# 05_POWER_2.net
KiCad netlist of a schematic drawn in Altium Designer
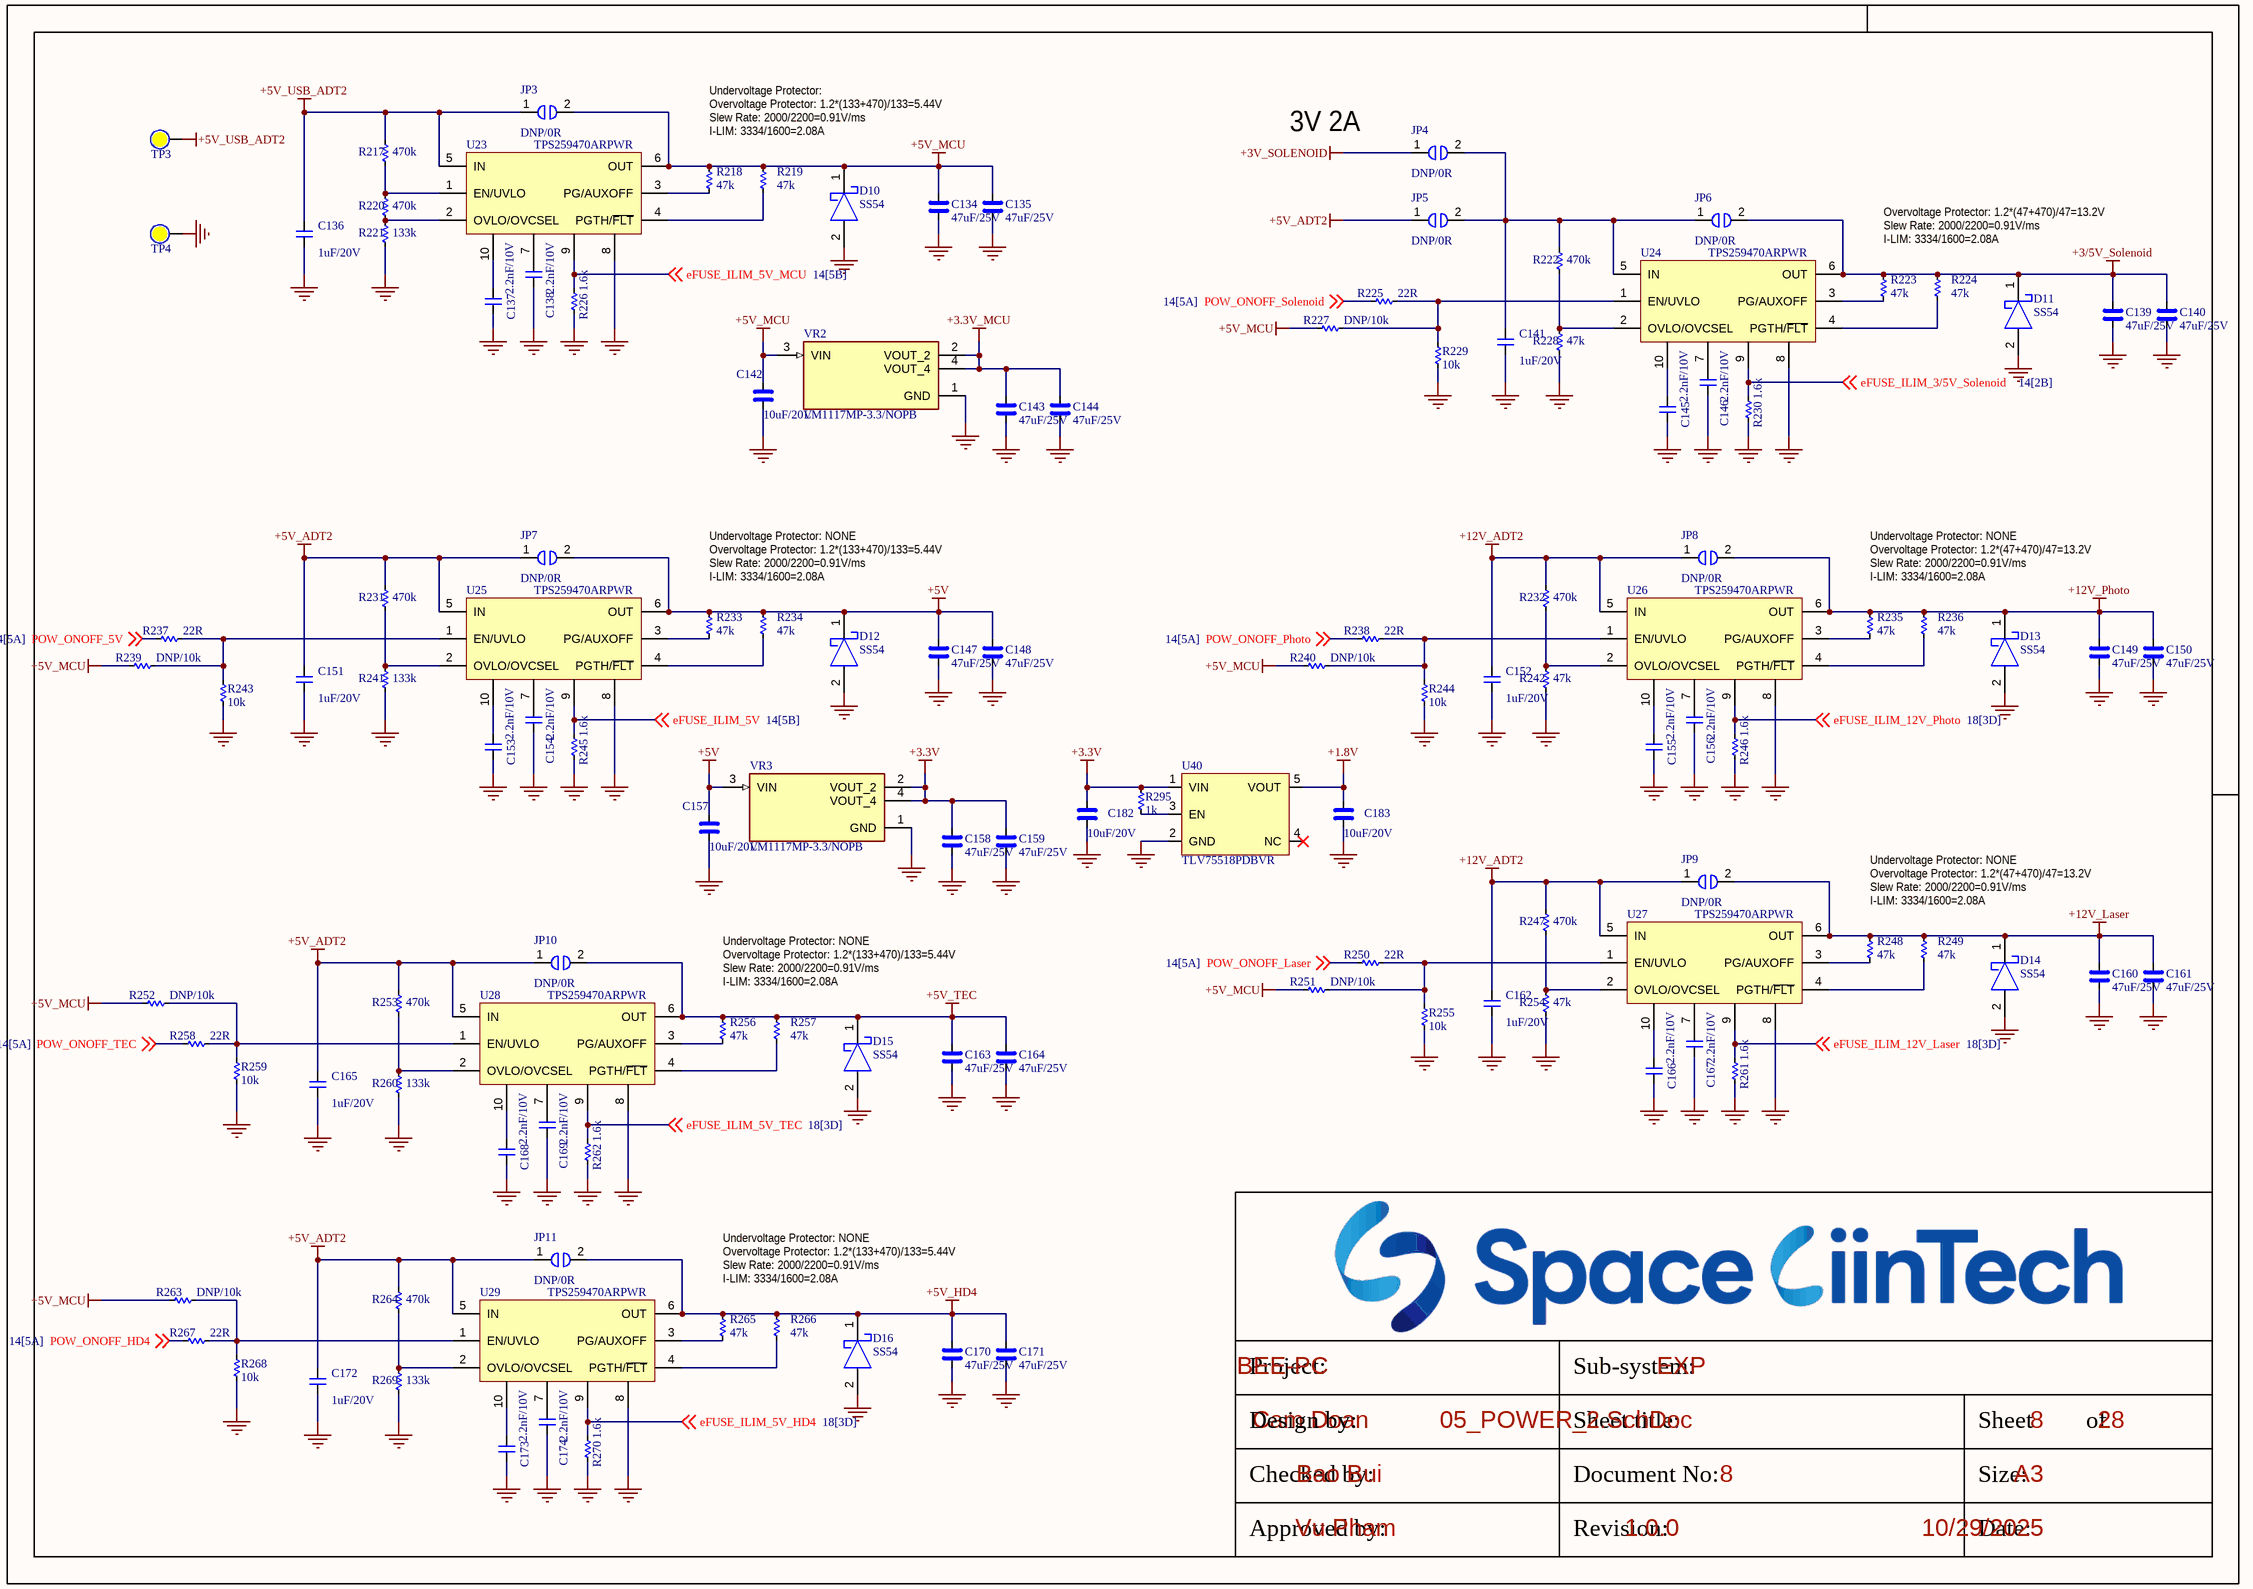
[diagram p0: 05_POWER_2.SchDoc]

(export (version "E")
  (design (tool "Eeschema 10.0.6"))
  (components
    (comp (ref "C134")
      (value "47uF/25V")
      (footprint "CAP_C_3225X80")
      (description "CAP CHIP High Value")
      (libsource (lib "LABLIB") (part "_CAP_C_High_2"))
    )
    (comp (ref "C135")
      (value "47uF/25V")
      (footprint "CAP_C_3225X80")
      (description "CAP CHIP High Value")
      (libsource (lib "LABLIB") (part "_CAP_C_High_2"))
    )
    (comp (ref "C136")
      (value "1uF/20V")
      (footprint "CAP_C_1005X60")
      (description "CAP CHIP")
      (libsource (lib "LABLIB") (part "_CAP_C_2"))
    )
    (comp (ref "C137")
      (value "2.2nF/10V")
      (footprint "CAP_C_1005X60")
      (description "CAP CHIP")
      (libsource (lib "LABLIB") (part "_CAP_C_2"))
    )
    (comp (ref "C138")
      (value "2.2nF/10V")
      (footprint "CAP_C_1005X60")
      (description "CAP CHIP")
      (libsource (lib "LABLIB") (part "_CAP_C_2"))
    )
    (comp (ref "C139")
      (value "47uF/25V")
      (footprint "CAP_C_3225X80")
      (description "CAP CHIP High Value")
      (libsource (lib "LABLIB") (part "_CAP_C_High_2"))
    )
    (comp (ref "C140")
      (value "47uF/25V")
      (footprint "CAP_C_3225X80")
      (description "CAP CHIP High Value")
      (libsource (lib "LABLIB") (part "_CAP_C_High_2"))
    )
    (comp (ref "C141")
      (value "1uF/20V")
      (footprint "CAP_C_1005X60")
      (description "CAP CHIP")
      (libsource (lib "LABLIB") (part "_CAP_C_2"))
    )
    (comp (ref "C142")
      (value "10uF/20V")
      (footprint "CAP_C_2012X110")
      (description "CAP CHIP High Value")
      (libsource (lib "LABLIB") (part "_CAP_C_High_2"))
    )
    (comp (ref "C143")
      (value "47uF/25V")
      (footprint "CAP_C_3225X80")
      (description "CAP CHIP High Value")
      (libsource (lib "LABLIB") (part "_CAP_C_High_2"))
    )
    (comp (ref "C144")
      (value "47uF/25V")
      (footprint "CAP_C_3225X80")
      (description "CAP CHIP High Value")
      (libsource (lib "LABLIB") (part "_CAP_C_High_2"))
    )
    (comp (ref "C145")
      (value "2.2nF/10V")
      (footprint "CAP_C_1005X60")
      (description "CAP CHIP")
      (libsource (lib "LABLIB") (part "_CAP_C_2"))
    )
    (comp (ref "C146")
      (value "2.2nF/10V")
      (footprint "CAP_C_1005X60")
      (description "CAP CHIP")
      (libsource (lib "LABLIB") (part "_CAP_C_2"))
    )
    (comp (ref "C147")
      (value "47uF/25V")
      (footprint "CAP_C_3225X80")
      (description "CAP CHIP High Value")
      (libsource (lib "LABLIB") (part "_CAP_C_High_2"))
    )
    (comp (ref "C148")
      (value "47uF/25V")
      (footprint "CAP_C_3225X80")
      (description "CAP CHIP High Value")
      (libsource (lib "LABLIB") (part "_CAP_C_High_2"))
    )
    (comp (ref "C149")
      (value "47uF/25V")
      (footprint "CAP_C_3225X80")
      (description "CAP CHIP High Value")
      (libsource (lib "LABLIB") (part "_CAP_C_High_2"))
    )
    (comp (ref "C150")
      (value "47uF/25V")
      (footprint "CAP_C_3225X80")
      (description "CAP CHIP High Value")
      (libsource (lib "LABLIB") (part "_CAP_C_High_2"))
    )
    (comp (ref "C151")
      (value "1uF/20V")
      (footprint "CAP_C_1005X60")
      (description "CAP CHIP")
      (libsource (lib "LABLIB") (part "_CAP_C_2"))
    )
    (comp (ref "C152")
      (value "1uF/20V")
      (footprint "CAP_C_1005X60")
      (description "CAP CHIP")
      (libsource (lib "LABLIB") (part "_CAP_C_2"))
    )
    (comp (ref "C153")
      (value "2.2nF/10V")
      (footprint "CAP_C_1005X60")
      (description "CAP CHIP")
      (libsource (lib "LABLIB") (part "_CAP_C_2"))
    )
    (comp (ref "C154")
      (value "2.2nF/10V")
      (footprint "CAP_C_1005X60")
      (description "CAP CHIP")
      (libsource (lib "LABLIB") (part "_CAP_C_2"))
    )
    (comp (ref "C155")
      (value "2.2nF/10V")
      (footprint "CAP_C_1005X60")
      (description "CAP CHIP")
      (libsource (lib "LABLIB") (part "_CAP_C_2"))
    )
    (comp (ref "C156")
      (value "2.2nF/10V")
      (footprint "CAP_C_1005X60")
      (description "CAP CHIP")
      (libsource (lib "LABLIB") (part "_CAP_C_2"))
    )
    (comp (ref "C157")
      (value "10uF/20V")
      (footprint "CAP_C_2012X110")
      (description "CAP CHIP High Value")
      (libsource (lib "LABLIB") (part "_CAP_C_High_2"))
    )
    (comp (ref "C158")
      (value "47uF/25V")
      (footprint "CAP_C_3225X80")
      (description "CAP CHIP High Value")
      (libsource (lib "LABLIB") (part "_CAP_C_High_2"))
    )
    (comp (ref "C159")
      (value "47uF/25V")
      (footprint "CAP_C_3225X80")
      (description "CAP CHIP High Value")
      (libsource (lib "LABLIB") (part "_CAP_C_High_2"))
    )
    (comp (ref "C160")
      (value "47uF/25V")
      (footprint "CAP_C_3225X80")
      (description "CAP CHIP High Value")
      (libsource (lib "LABLIB") (part "_CAP_C_High_2"))
    )
    (comp (ref "C161")
      (value "47uF/25V")
      (footprint "CAP_C_3225X80")
      (description "CAP CHIP High Value")
      (libsource (lib "LABLIB") (part "_CAP_C_High_2"))
    )
    (comp (ref "C162")
      (value "1uF/20V")
      (footprint "CAP_C_1005X60")
      (description "CAP CHIP")
      (libsource (lib "LABLIB") (part "_CAP_C_2"))
    )
    (comp (ref "C163")
      (value "47uF/25V")
      (footprint "CAP_C_3225X80")
      (description "CAP CHIP High Value")
      (libsource (lib "LABLIB") (part "_CAP_C_High_2"))
    )
    (comp (ref "C164")
      (value "47uF/25V")
      (footprint "CAP_C_3225X80")
      (description "CAP CHIP High Value")
      (libsource (lib "LABLIB") (part "_CAP_C_High_2"))
    )
    (comp (ref "C165")
      (value "1uF/20V")
      (footprint "CAP_C_1005X60")
      (description "CAP CHIP")
      (libsource (lib "LABLIB") (part "_CAP_C_2"))
    )
    (comp (ref "C166")
      (value "2.2nF/10V")
      (footprint "CAP_C_1005X60")
      (description "CAP CHIP")
      (libsource (lib "LABLIB") (part "_CAP_C_2"))
    )
    (comp (ref "C167")
      (value "2.2nF/10V")
      (footprint "CAP_C_1005X60")
      (description "CAP CHIP")
      (libsource (lib "LABLIB") (part "_CAP_C_2"))
    )
    (comp (ref "C168")
      (value "2.2nF/10V")
      (footprint "CAP_C_1005X60")
      (description "CAP CHIP")
      (libsource (lib "LABLIB") (part "_CAP_C_2"))
    )
    (comp (ref "C169")
      (value "2.2nF/10V")
      (footprint "CAP_C_1005X60")
      (description "CAP CHIP")
      (libsource (lib "LABLIB") (part "_CAP_C_2"))
    )
    (comp (ref "C170")
      (value "47uF/25V")
      (footprint "CAP_C_3225X80")
      (description "CAP CHIP High Value")
      (libsource (lib "LABLIB") (part "_CAP_C_High_2"))
    )
    (comp (ref "C171")
      (value "47uF/25V")
      (footprint "CAP_C_3225X80")
      (description "CAP CHIP High Value")
      (libsource (lib "LABLIB") (part "_CAP_C_High_2"))
    )
    (comp (ref "C172")
      (value "1uF/20V")
      (footprint "CAP_C_1005X60")
      (description "CAP CHIP")
      (libsource (lib "LABLIB") (part "_CAP_C_2"))
    )
    (comp (ref "C173")
      (value "2.2nF/10V")
      (footprint "CAP_C_1005X60")
      (description "CAP CHIP")
      (libsource (lib "LABLIB") (part "_CAP_C_2"))
    )
    (comp (ref "C174")
      (value "2.2nF/10V")
      (footprint "CAP_C_1005X60")
      (description "CAP CHIP")
      (libsource (lib "LABLIB") (part "_CAP_C_2"))
    )
    (comp (ref "C182")
      (value "10uF/20V")
      (footprint "CAP_C_2012X110")
      (description "CAP CHIP High Value")
      (libsource (lib "LABLIB") (part "_CAP_C_High_2"))
    )
    (comp (ref "C183")
      (value "10uF/20V")
      (footprint "CAP_C_2012X110")
      (description "CAP CHIP High Value")
      (libsource (lib "LABLIB") (part "_CAP_C_High_2"))
    )
    (comp (ref "D10")
      (value "SS54")
      (footprint "DO-214AC_SMA")
      (description "DIODE SCHOTTKY 60V 3A DO214AA")
      (libsource (lib "EXP_HW_V3") (part "SS54"))
    )
    (comp (ref "D11")
      (value "SS54")
      (footprint "DO-214AC_SMA")
      (description "DIODE SCHOTTKY 60V 3A DO214AA")
      (libsource (lib "EXP_HW_V3") (part "SS54"))
    )
    (comp (ref "D12")
      (value "SS54")
      (footprint "DO-214AC_SMA")
      (description "DIODE SCHOTTKY 60V 3A DO214AA")
      (libsource (lib "EXP_HW_V3") (part "SS54"))
    )
    (comp (ref "D13")
      (value "SS54")
      (footprint "DO-214AC_SMA")
      (description "DIODE SCHOTTKY 60V 3A DO214AA")
      (libsource (lib "EXP_HW_V3") (part "SS54"))
    )
    (comp (ref "D14")
      (value "SS54")
      (footprint "DO-214AC_SMA")
      (description "DIODE SCHOTTKY 60V 3A DO214AA")
      (libsource (lib "EXP_HW_V3") (part "SS54"))
    )
    (comp (ref "D15")
      (value "SS54")
      (footprint "DO-214AC_SMA")
      (description "DIODE SCHOTTKY 60V 3A DO214AA")
      (libsource (lib "EXP_HW_V3") (part "SS54"))
    )
    (comp (ref "D16")
      (value "SS54")
      (footprint "DO-214AC_SMA")
      (description "DIODE SCHOTTKY 60V 3A DO214AA")
      (libsource (lib "EXP_HW_V3") (part "SS54"))
    )
    (comp (ref "JP3")
      (value "DNP/0R")
      (footprint "RES_C_1608X60")
      (libsource (lib "LABLIB") (part "JUMPER_1_1"))
    )
    (comp (ref "JP4")
      (value "DNP/0R")
      (footprint "RES_C_1608X60")
      (libsource (lib "LABLIB") (part "JUMPER_1_1"))
    )
    (comp (ref "JP5")
      (value "DNP/0R")
      (footprint "RES_C_1608X60")
      (libsource (lib "LABLIB") (part "JUMPER_1_1"))
    )
    (comp (ref "JP6")
      (value "DNP/0R")
      (footprint "RES_C_1608X60")
      (libsource (lib "LABLIB") (part "JUMPER_1_1"))
    )
    (comp (ref "JP7")
      (value "DNP/0R")
      (footprint "RES_C_1608X60")
      (libsource (lib "LABLIB") (part "JUMPER_1_1"))
    )
    (comp (ref "JP8")
      (value "DNP/0R")
      (footprint "RES_C_1608X60")
      (libsource (lib "LABLIB") (part "JUMPER_1_1"))
    )
    (comp (ref "JP9")
      (value "DNP/0R")
      (footprint "RES_C_1608X60")
      (libsource (lib "LABLIB") (part "JUMPER_1_1"))
    )
    (comp (ref "JP10")
      (value "DNP/0R")
      (footprint "RES_C_1608X60")
      (libsource (lib "LABLIB") (part "JUMPER_1_1"))
    )
    (comp (ref "JP11")
      (value "DNP/0R")
      (footprint "RES_C_1608X60")
      (libsource (lib "LABLIB") (part "JUMPER_1_1"))
    )
    (comp (ref "R217")
      (value "470k")
      (footprint "RES_C_1005X40")
      (description "RES")
      (libsource (lib "LABLIB") (part "_RES_B_2"))
    )
    (comp (ref "R218")
      (value "47k")
      (footprint "RES_C_1005X40")
      (description "RES")
      (libsource (lib "LABLIB") (part "_RES_B_2"))
    )
    (comp (ref "R219")
      (value "47k")
      (footprint "RES_C_1005X40")
      (description "RES")
      (libsource (lib "LABLIB") (part "_RES_B_2"))
    )
    (comp (ref "R220")
      (value "470k")
      (footprint "RES_C_1005X40")
      (description "RES")
      (libsource (lib "LABLIB") (part "_RES_B_2"))
    )
    (comp (ref "R221")
      (value "133k")
      (footprint "RES_C_1005X40")
      (description "RES")
      (libsource (lib "LABLIB") (part "_RES_B_2"))
    )
    (comp (ref "R222")
      (value "470k")
      (footprint "RES_C_1005X40")
      (description "RES")
      (libsource (lib "LABLIB") (part "_RES_B_2"))
    )
    (comp (ref "R223")
      (value "47k")
      (footprint "RES_C_1005X40")
      (description "RES")
      (libsource (lib "LABLIB") (part "_RES_B_2"))
    )
    (comp (ref "R224")
      (value "47k")
      (footprint "RES_C_1005X40")
      (description "RES")
      (libsource (lib "LABLIB") (part "_RES_B_2"))
    )
    (comp (ref "R225")
      (value "22R")
      (footprint "RES_C_1005X40")
      (description "RES")
      (libsource (lib "LABLIB") (part "_RES_B_2"))
    )
    (comp (ref "R226")
      (value "1.6k")
      (footprint "RES_C_1005X40")
      (description "RES")
      (libsource (lib "LABLIB") (part "_RES_B_2"))
    )
    (comp (ref "R227")
      (value "DNP/10k")
      (footprint "RES_C_1005X40")
      (description "RES")
      (libsource (lib "LABLIB") (part "_RES_B_2"))
    )
    (comp (ref "R228")
      (value "47k")
      (footprint "RES_C_1005X40")
      (description "RES")
      (libsource (lib "LABLIB") (part "_RES_B_2"))
    )
    (comp (ref "R229")
      (value "10k")
      (footprint "RES_C_1005X40")
      (description "RES")
      (libsource (lib "LABLIB") (part "_RES_B_2"))
    )
    (comp (ref "R230")
      (value "1.6k")
      (footprint "RES_C_1005X40")
      (description "RES")
      (libsource (lib "LABLIB") (part "_RES_B_2"))
    )
    (comp (ref "R231")
      (value "470k")
      (footprint "RES_C_1005X40")
      (description "RES")
      (libsource (lib "LABLIB") (part "_RES_B_2"))
    )
    (comp (ref "R232")
      (value "470k")
      (footprint "RES_C_1005X40")
      (description "RES")
      (libsource (lib "LABLIB") (part "_RES_B_2"))
    )
    (comp (ref "R233")
      (value "47k")
      (footprint "RES_C_1005X40")
      (description "RES")
      (libsource (lib "LABLIB") (part "_RES_B_2"))
    )
    (comp (ref "R234")
      (value "47k")
      (footprint "RES_C_1005X40")
      (description "RES")
      (libsource (lib "LABLIB") (part "_RES_B_2"))
    )
    (comp (ref "R235")
      (value "47k")
      (footprint "RES_C_1005X40")
      (description "RES")
      (libsource (lib "LABLIB") (part "_RES_B_2"))
    )
    (comp (ref "R236")
      (value "47k")
      (footprint "RES_C_1005X40")
      (description "RES")
      (libsource (lib "LABLIB") (part "_RES_B_2"))
    )
    (comp (ref "R237")
      (value "22R")
      (footprint "RES_C_1005X40")
      (description "RES")
      (libsource (lib "LABLIB") (part "_RES_B_2"))
    )
    (comp (ref "R238")
      (value "22R")
      (footprint "RES_C_1005X40")
      (description "RES")
      (libsource (lib "LABLIB") (part "_RES_B_2"))
    )
    (comp (ref "R239")
      (value "DNP/10k")
      (footprint "RES_C_1005X40")
      (description "RES")
      (libsource (lib "LABLIB") (part "_RES_B_2"))
    )
    (comp (ref "R240")
      (value "DNP/10k")
      (footprint "RES_C_1005X40")
      (description "RES")
      (libsource (lib "LABLIB") (part "_RES_B_2"))
    )
    (comp (ref "R241")
      (value "133k")
      (footprint "RES_C_1005X40")
      (description "RES")
      (libsource (lib "LABLIB") (part "_RES_B_2"))
    )
    (comp (ref "R242")
      (value "47k")
      (footprint "RES_C_1005X40")
      (description "RES")
      (libsource (lib "LABLIB") (part "_RES_B_2"))
    )
    (comp (ref "R243")
      (value "10k")
      (footprint "RES_C_1005X40")
      (description "RES")
      (libsource (lib "LABLIB") (part "_RES_B_2"))
    )
    (comp (ref "R244")
      (value "10k")
      (footprint "RES_C_1005X40")
      (description "RES")
      (libsource (lib "LABLIB") (part "_RES_B_2"))
    )
    (comp (ref "R245")
      (value "1.6k")
      (footprint "RES_C_1005X40")
      (description "RES")
      (libsource (lib "LABLIB") (part "_RES_B_2"))
    )
    (comp (ref "R246")
      (value "1.6k")
      (footprint "RES_C_1005X40")
      (description "RES")
      (libsource (lib "LABLIB") (part "_RES_B_2"))
    )
    (comp (ref "R247")
      (value "470k")
      (footprint "RES_C_1005X40")
      (description "RES")
      (libsource (lib "LABLIB") (part "_RES_B_2"))
    )
    (comp (ref "R248")
      (value "47k")
      (footprint "RES_C_1005X40")
      (description "RES")
      (libsource (lib "LABLIB") (part "_RES_B_2"))
    )
    (comp (ref "R249")
      (value "47k")
      (footprint "RES_C_1005X40")
      (description "RES")
      (libsource (lib "LABLIB") (part "_RES_B_2"))
    )
    (comp (ref "R250")
      (value "22R")
      (footprint "RES_C_1005X40")
      (description "RES")
      (libsource (lib "LABLIB") (part "_RES_B_2"))
    )
    (comp (ref "R251")
      (value "DNP/10k")
      (footprint "RES_C_1005X40")
      (description "RES")
      (libsource (lib "LABLIB") (part "_RES_B_2"))
    )
    (comp (ref "R252")
      (value "DNP/10k")
      (footprint "RES_C_1005X40")
      (description "RES")
      (libsource (lib "LABLIB") (part "_RES_B_2"))
    )
    (comp (ref "R253")
      (value "470k")
      (footprint "RES_C_1005X40")
      (description "RES")
      (libsource (lib "LABLIB") (part "_RES_B_2"))
    )
    (comp (ref "R254")
      (value "47k")
      (footprint "RES_C_1005X40")
      (description "RES")
      (libsource (lib "LABLIB") (part "_RES_B_2"))
    )
    (comp (ref "R255")
      (value "10k")
      (footprint "RES_C_1005X40")
      (description "RES")
      (libsource (lib "LABLIB") (part "_RES_B_2"))
    )
    (comp (ref "R256")
      (value "47k")
      (footprint "RES_C_1005X40")
      (description "RES")
      (libsource (lib "LABLIB") (part "_RES_B_2"))
    )
    (comp (ref "R257")
      (value "47k")
      (footprint "RES_C_1005X40")
      (description "RES")
      (libsource (lib "LABLIB") (part "_RES_B_2"))
    )
    (comp (ref "R258")
      (value "22R")
      (footprint "RES_C_1005X40")
      (description "RES")
      (libsource (lib "LABLIB") (part "_RES_B_2"))
    )
    (comp (ref "R259")
      (value "10k")
      (footprint "RES_C_1005X40")
      (description "RES")
      (libsource (lib "LABLIB") (part "_RES_B_2"))
    )
    (comp (ref "R260")
      (value "133k")
      (footprint "RES_C_1005X40")
      (description "RES")
      (libsource (lib "LABLIB") (part "_RES_B_2"))
    )
    (comp (ref "R261")
      (value "1.6k")
      (footprint "RES_C_1005X40")
      (description "RES")
      (libsource (lib "LABLIB") (part "_RES_B_2"))
    )
    (comp (ref "R262")
      (value "1.6k")
      (footprint "RES_C_1005X40")
      (description "RES")
      (libsource (lib "LABLIB") (part "_RES_B_2"))
    )
    (comp (ref "R263")
      (value "DNP/10k")
      (footprint "RES_C_1005X40")
      (description "RES")
      (libsource (lib "LABLIB") (part "_RES_B_2"))
    )
    (comp (ref "R264")
      (value "470k")
      (footprint "RES_C_1005X40")
      (description "RES")
      (libsource (lib "LABLIB") (part "_RES_B_2"))
    )
    (comp (ref "R265")
      (value "47k")
      (footprint "RES_C_1005X40")
      (description "RES")
      (libsource (lib "LABLIB") (part "_RES_B_2"))
    )
    (comp (ref "R266")
      (value "47k")
      (footprint "RES_C_1005X40")
      (description "RES")
      (libsource (lib "LABLIB") (part "_RES_B_2"))
    )
    (comp (ref "R267")
      (value "22R")
      (footprint "RES_C_1005X40")
      (description "RES")
      (libsource (lib "LABLIB") (part "_RES_B_2"))
    )
    (comp (ref "R268")
      (value "10k")
      (footprint "RES_C_1005X40")
      (description "RES")
      (libsource (lib "LABLIB") (part "_RES_B_2"))
    )
    (comp (ref "R269")
      (value "133k")
      (footprint "RES_C_1005X40")
      (description "RES")
      (libsource (lib "LABLIB") (part "_RES_B_2"))
    )
    (comp (ref "R270")
      (value "1.6k")
      (footprint "RES_C_1005X40")
      (description "RES")
      (libsource (lib "LABLIB") (part "_RES_B_2"))
    )
    (comp (ref "R295")
      (value "1k")
      (footprint "RES_C_1005X40")
      (description "RES")
      (libsource (lib "LABLIB") (part "_RES_B_2"))
    )
    (comp (ref "TP3")
      (value "~")
      (footprint "Testpoint_TH_D130H80")
      (description "Test Point")
      (libsource (lib "LABLIB") (part "Test Point"))
    )
    (comp (ref "TP4")
      (value "~")
      (footprint "Testpoint_TH_D130H80")
      (description "Test Point")
      (libsource (lib "LABLIB") (part "Test Point"))
    )
    (comp (ref "U23")
      (value "TPS259470ARPWR")
      (footprint "VQFN-HR-10")
      (libsource (lib "EXP_HW_V3") (part "TPS259470ARPWR"))
    )
    (comp (ref "U24")
      (value "TPS259470ARPWR")
      (footprint "VQFN-HR-10")
      (libsource (lib "EXP_HW_V3") (part "TPS259470ARPWR"))
    )
    (comp (ref "U25")
      (value "TPS259470ARPWR")
      (footprint "VQFN-HR-10")
      (libsource (lib "EXP_HW_V3") (part "TPS259470ARPWR"))
    )
    (comp (ref "U26")
      (value "TPS259470ARPWR")
      (footprint "VQFN-HR-10")
      (libsource (lib "EXP_HW_V3") (part "TPS259470ARPWR"))
    )
    (comp (ref "U27")
      (value "TPS259470ARPWR")
      (footprint "VQFN-HR-10")
      (libsource (lib "EXP_HW_V3") (part "TPS259470ARPWR"))
    )
    (comp (ref "U28")
      (value "TPS259470ARPWR")
      (footprint "VQFN-HR-10")
      (libsource (lib "EXP_HW_V3") (part "TPS259470ARPWR"))
    )
    (comp (ref "U29")
      (value "TPS259470ARPWR")
      (footprint "VQFN-HR-10")
      (libsource (lib "EXP_HW_V3") (part "TPS259470ARPWR"))
    )
    (comp (ref "U40")
      (value "TLV75518PDBVR")
      (footprint "SOT25")
      (libsource (lib "CAMERA_SchLib") (part "IC_POWER_AP7347DQ"))
    )
    (comp (ref "VR2")
      (value "LM1117MP-3.3/NOPB")
      (footprint "VREG_LM1117MP-3.3/NOPB")
      (description "800-mA 15-V linear voltage regulator")
      (fields (field (name "MF") "Texas Instruments"))
      (libsource (lib "new_component") (part "LM1117MP-3.3/NOPB"))
    )
    (comp (ref "VR3")
      (value "LM1117MP-3.3/NOPB")
      (footprint "VREG_LM1117MP-3.3/NOPB")
      (description "800-mA 15-V linear voltage regulator")
      (fields (field (name "MF") "Texas Instruments"))
      (libsource (lib "new_component") (part "LM1117MP-3.3/NOPB"))
    )
  )
  (nets
    (net (code "1") (name "+1.8V") (class "Default")
      (node (ref "C183") (pin "1") (pinfunction "1_1") (pintype "passive"))
      (node (ref "U40") (pin "5") (pinfunction "VOUT_5") (pintype "passive"))
    )
    (net (code "2") (name "+3.3V") (class "Default")
      (node (ref "C158") (pin "2") (pinfunction "2_2") (pintype "passive"))
      (node (ref "C159") (pin "2") (pinfunction "2_2") (pintype "passive"))
      (node (ref "C182") (pin "1") (pinfunction "1_1") (pintype "passive"))
      (node (ref "R295") (pin "2") (pinfunction "2_2") (pintype "passive"))
      (node (ref "U40") (pin "1") (pinfunction "VIN_1") (pintype "passive"))
      (node (ref "VR3") (pin "2") (pinfunction "VOUT_2_2") (pintype "power_in"))
      (node (ref "VR3") (pin "4") (pinfunction "VOUT_4_4") (pintype "power_in"))
    )
    (net (code "3") (name "+3.3V_MCU") (class "Default")
      (node (ref "C143") (pin "2") (pinfunction "2_2") (pintype "passive"))
      (node (ref "C144") (pin "2") (pinfunction "2_2") (pintype "passive"))
      (node (ref "VR2") (pin "2") (pinfunction "VOUT_2_2") (pintype "power_in"))
      (node (ref "VR2") (pin "4") (pinfunction "VOUT_4_4") (pintype "power_in"))
    )
    (net (code "4") (name "+3V_SOLENOID") (class "Default")
      (node (ref "JP4") (pin "1") (pinfunction "1_1") (pintype "passive"))
    )
    (net (code "5") (name "+3{slash}5V_Solenoid") (class "Default")
      (node (ref "C139") (pin "2") (pinfunction "2_2") (pintype "passive"))
      (node (ref "C140") (pin "2") (pinfunction "2_2") (pintype "passive"))
      (node (ref "D11") (pin "1") (pinfunction "1_1") (pintype "passive"))
      (node (ref "JP6") (pin "2") (pinfunction "2_2") (pintype "passive"))
      (node (ref "R223") (pin "2") (pinfunction "2_2") (pintype "passive"))
      (node (ref "R224") (pin "2") (pinfunction "2_2") (pintype "passive"))
      (node (ref "U24") (pin "6") (pinfunction "OUT_6") (pintype "passive"))
    )
    (net (code "6") (name "+5V") (class "Default")
      (node (ref "C147") (pin "2") (pinfunction "2_2") (pintype "passive"))
      (node (ref "C148") (pin "2") (pinfunction "2_2") (pintype "passive"))
      (node (ref "C157") (pin "1") (pinfunction "1_1") (pintype "passive"))
      (node (ref "D12") (pin "1") (pinfunction "1_1") (pintype "passive"))
      (node (ref "JP7") (pin "2") (pinfunction "2_2") (pintype "passive"))
      (node (ref "R233") (pin "2") (pinfunction "2_2") (pintype "passive"))
      (node (ref "R234") (pin "2") (pinfunction "2_2") (pintype "passive"))
      (node (ref "U25") (pin "6") (pinfunction "OUT_6") (pintype "passive"))
      (node (ref "VR3") (pin "3") (pinfunction "VIN_3") (pintype "input"))
    )
    (net (code "7") (name "+5V_ADT2") (class "Default")
      (node (ref "C151") (pin "2") (pinfunction "2_2") (pintype "passive"))
      (node (ref "C165") (pin "2") (pinfunction "2_2") (pintype "passive"))
      (node (ref "C172") (pin "2") (pinfunction "2_2") (pintype "passive"))
      (node (ref "JP10") (pin "1") (pinfunction "1_1") (pintype "passive"))
      (node (ref "JP11") (pin "1") (pinfunction "1_1") (pintype "passive"))
      (node (ref "JP5") (pin "1") (pinfunction "1_1") (pintype "passive"))
      (node (ref "JP7") (pin "1") (pinfunction "1_1") (pintype "passive"))
      (node (ref "R231") (pin "2") (pinfunction "2_2") (pintype "passive"))
      (node (ref "R253") (pin "2") (pinfunction "2_2") (pintype "passive"))
      (node (ref "R264") (pin "2") (pinfunction "2_2") (pintype "passive"))
      (node (ref "U25") (pin "5") (pinfunction "IN_5") (pintype "passive"))
      (node (ref "U28") (pin "5") (pinfunction "IN_5") (pintype "passive"))
      (node (ref "U29") (pin "5") (pinfunction "IN_5") (pintype "passive"))
    )
    (net (code "8") (name "+5V_HD4") (class "Default")
      (node (ref "C170") (pin "2") (pinfunction "2_2") (pintype "passive"))
      (node (ref "C171") (pin "2") (pinfunction "2_2") (pintype "passive"))
      (node (ref "D16") (pin "1") (pinfunction "1_1") (pintype "passive"))
      (node (ref "JP11") (pin "2") (pinfunction "2_2") (pintype "passive"))
      (node (ref "R265") (pin "2") (pinfunction "2_2") (pintype "passive"))
      (node (ref "R266") (pin "2") (pinfunction "2_2") (pintype "passive"))
      (node (ref "U29") (pin "6") (pinfunction "OUT_6") (pintype "passive"))
    )
    (net (code "9") (name "+5V_MCU") (class "Default")
      (node (ref "C134") (pin "2") (pinfunction "2_2") (pintype "passive"))
      (node (ref "C135") (pin "2") (pinfunction "2_2") (pintype "passive"))
      (node (ref "C142") (pin "1") (pinfunction "1_1") (pintype "passive"))
      (node (ref "D10") (pin "1") (pinfunction "1_1") (pintype "passive"))
      (node (ref "JP3") (pin "2") (pinfunction "2_2") (pintype "passive"))
      (node (ref "R218") (pin "2") (pinfunction "2_2") (pintype "passive"))
      (node (ref "R219") (pin "2") (pinfunction "2_2") (pintype "passive"))
      (node (ref "R227") (pin "2") (pinfunction "2_2") (pintype "passive"))
      (node (ref "R239") (pin "2") (pinfunction "2_2") (pintype "passive"))
      (node (ref "R240") (pin "2") (pinfunction "2_2") (pintype "passive"))
      (node (ref "R251") (pin "2") (pinfunction "2_2") (pintype "passive"))
      (node (ref "R252") (pin "2") (pinfunction "2_2") (pintype "passive"))
      (node (ref "R263") (pin "2") (pinfunction "2_2") (pintype "passive"))
      (node (ref "U23") (pin "6") (pinfunction "OUT_6") (pintype "passive"))
      (node (ref "VR2") (pin "3") (pinfunction "VIN_3") (pintype "input"))
    )
    (net (code "10") (name "+5V_TEC") (class "Default")
      (node (ref "C163") (pin "2") (pinfunction "2_2") (pintype "passive"))
      (node (ref "C164") (pin "2") (pinfunction "2_2") (pintype "passive"))
      (node (ref "D15") (pin "1") (pinfunction "1_1") (pintype "passive"))
      (node (ref "JP10") (pin "2") (pinfunction "2_2") (pintype "passive"))
      (node (ref "R256") (pin "2") (pinfunction "2_2") (pintype "passive"))
      (node (ref "R257") (pin "2") (pinfunction "2_2") (pintype "passive"))
      (node (ref "U28") (pin "6") (pinfunction "OUT_6") (pintype "passive"))
    )
    (net (code "11") (name "+5V_USB_ADT2") (class "Default")
      (node (ref "C136") (pin "2") (pinfunction "2_2") (pintype "passive"))
      (node (ref "JP3") (pin "1") (pinfunction "1_1") (pintype "passive"))
      (node (ref "R217") (pin "2") (pinfunction "2_2") (pintype "passive"))
      (node (ref "TP3") (pin "0") (pinfunction "0_0") (pintype "passive"))
      (node (ref "U23") (pin "5") (pinfunction "IN_5") (pintype "passive"))
    )
    (net (code "12") (name "+12V_ADT2") (class "Default")
      (node (ref "C152") (pin "2") (pinfunction "2_2") (pintype "passive"))
      (node (ref "C162") (pin "2") (pinfunction "2_2") (pintype "passive"))
      (node (ref "JP8") (pin "1") (pinfunction "1_1") (pintype "passive"))
      (node (ref "JP9") (pin "1") (pinfunction "1_1") (pintype "passive"))
      (node (ref "R232") (pin "2") (pinfunction "2_2") (pintype "passive"))
      (node (ref "R247") (pin "2") (pinfunction "2_2") (pintype "passive"))
      (node (ref "U26") (pin "5") (pinfunction "IN_5") (pintype "passive"))
      (node (ref "U27") (pin "5") (pinfunction "IN_5") (pintype "passive"))
    )
    (net (code "13") (name "+12V_Laser") (class "Default")
      (node (ref "C160") (pin "2") (pinfunction "2_2") (pintype "passive"))
      (node (ref "C161") (pin "2") (pinfunction "2_2") (pintype "passive"))
      (node (ref "D14") (pin "1") (pinfunction "1_1") (pintype "passive"))
      (node (ref "JP9") (pin "2") (pinfunction "2_2") (pintype "passive"))
      (node (ref "R248") (pin "2") (pinfunction "2_2") (pintype "passive"))
      (node (ref "R249") (pin "2") (pinfunction "2_2") (pintype "passive"))
      (node (ref "U27") (pin "6") (pinfunction "OUT_6") (pintype "passive"))
    )
    (net (code "14") (name "+12V_Photo") (class "Default")
      (node (ref "C149") (pin "2") (pinfunction "2_2") (pintype "passive"))
      (node (ref "C150") (pin "2") (pinfunction "2_2") (pintype "passive"))
      (node (ref "D13") (pin "1") (pinfunction "1_1") (pintype "passive"))
      (node (ref "JP8") (pin "2") (pinfunction "2_2") (pintype "passive"))
      (node (ref "R235") (pin "2") (pinfunction "2_2") (pintype "passive"))
      (node (ref "R236") (pin "2") (pinfunction "2_2") (pintype "passive"))
      (node (ref "U26") (pin "6") (pinfunction "OUT_6") (pintype "passive"))
    )
    (net (code "15") (name "GND") (class "Default")
      (node (ref "C134") (pin "1") (pinfunction "1_1") (pintype "passive"))
      (node (ref "C135") (pin "1") (pinfunction "1_1") (pintype "passive"))
      (node (ref "C136") (pin "1") (pinfunction "1_1") (pintype "passive"))
      (node (ref "C137") (pin "1") (pinfunction "1_1") (pintype "passive"))
      (node (ref "C138") (pin "1") (pinfunction "1_1") (pintype "passive"))
      (node (ref "C139") (pin "1") (pinfunction "1_1") (pintype "passive"))
      (node (ref "C140") (pin "1") (pinfunction "1_1") (pintype "passive"))
      (node (ref "C141") (pin "1") (pinfunction "1_1") (pintype "passive"))
      (node (ref "C142") (pin "2") (pinfunction "2_2") (pintype "passive"))
      (node (ref "C143") (pin "1") (pinfunction "1_1") (pintype "passive"))
      (node (ref "C144") (pin "1") (pinfunction "1_1") (pintype "passive"))
      (node (ref "C145") (pin "1") (pinfunction "1_1") (pintype "passive"))
      (node (ref "C146") (pin "1") (pinfunction "1_1") (pintype "passive"))
      (node (ref "C147") (pin "1") (pinfunction "1_1") (pintype "passive"))
      (node (ref "C148") (pin "1") (pinfunction "1_1") (pintype "passive"))
      (node (ref "C149") (pin "1") (pinfunction "1_1") (pintype "passive"))
      (node (ref "C150") (pin "1") (pinfunction "1_1") (pintype "passive"))
      (node (ref "C151") (pin "1") (pinfunction "1_1") (pintype "passive"))
      (node (ref "C152") (pin "1") (pinfunction "1_1") (pintype "passive"))
      (node (ref "C153") (pin "1") (pinfunction "1_1") (pintype "passive"))
      (node (ref "C154") (pin "1") (pinfunction "1_1") (pintype "passive"))
      (node (ref "C155") (pin "1") (pinfunction "1_1") (pintype "passive"))
      (node (ref "C156") (pin "1") (pinfunction "1_1") (pintype "passive"))
      (node (ref "C157") (pin "2") (pinfunction "2_2") (pintype "passive"))
      (node (ref "C158") (pin "1") (pinfunction "1_1") (pintype "passive"))
      (node (ref "C159") (pin "1") (pinfunction "1_1") (pintype "passive"))
      (node (ref "C160") (pin "1") (pinfunction "1_1") (pintype "passive"))
      (node (ref "C161") (pin "1") (pinfunction "1_1") (pintype "passive"))
      (node (ref "C162") (pin "1") (pinfunction "1_1") (pintype "passive"))
      (node (ref "C163") (pin "1") (pinfunction "1_1") (pintype "passive"))
      (node (ref "C164") (pin "1") (pinfunction "1_1") (pintype "passive"))
      (node (ref "C165") (pin "1") (pinfunction "1_1") (pintype "passive"))
      (node (ref "C166") (pin "1") (pinfunction "1_1") (pintype "passive"))
      (node (ref "C167") (pin "1") (pinfunction "1_1") (pintype "passive"))
      (node (ref "C168") (pin "1") (pinfunction "1_1") (pintype "passive"))
      (node (ref "C169") (pin "1") (pinfunction "1_1") (pintype "passive"))
      (node (ref "C170") (pin "1") (pinfunction "1_1") (pintype "passive"))
      (node (ref "C171") (pin "1") (pinfunction "1_1") (pintype "passive"))
      (node (ref "C172") (pin "1") (pinfunction "1_1") (pintype "passive"))
      (node (ref "C173") (pin "1") (pinfunction "1_1") (pintype "passive"))
      (node (ref "C174") (pin "1") (pinfunction "1_1") (pintype "passive"))
      (node (ref "C182") (pin "2") (pinfunction "2_2") (pintype "passive"))
      (node (ref "C183") (pin "2") (pinfunction "2_2") (pintype "passive"))
      (node (ref "D10") (pin "2") (pinfunction "2_2") (pintype "passive"))
      (node (ref "D11") (pin "2") (pinfunction "2_2") (pintype "passive"))
      (node (ref "D12") (pin "2") (pinfunction "2_2") (pintype "passive"))
      (node (ref "D13") (pin "2") (pinfunction "2_2") (pintype "passive"))
      (node (ref "D14") (pin "2") (pinfunction "2_2") (pintype "passive"))
      (node (ref "D15") (pin "2") (pinfunction "2_2") (pintype "passive"))
      (node (ref "D16") (pin "2") (pinfunction "2_2") (pintype "passive"))
      (node (ref "R221") (pin "1") (pinfunction "1_1") (pintype "passive"))
      (node (ref "R226") (pin "1") (pinfunction "1_1") (pintype "passive"))
      (node (ref "R228") (pin "1") (pinfunction "1_1") (pintype "passive"))
      (node (ref "R229") (pin "2") (pinfunction "2_2") (pintype "passive"))
      (node (ref "R230") (pin "1") (pinfunction "1_1") (pintype "passive"))
      (node (ref "R241") (pin "1") (pinfunction "1_1") (pintype "passive"))
      (node (ref "R242") (pin "1") (pinfunction "1_1") (pintype "passive"))
      (node (ref "R243") (pin "2") (pinfunction "2_2") (pintype "passive"))
      (node (ref "R244") (pin "2") (pinfunction "2_2") (pintype "passive"))
      (node (ref "R245") (pin "1") (pinfunction "1_1") (pintype "passive"))
      (node (ref "R246") (pin "1") (pinfunction "1_1") (pintype "passive"))
      (node (ref "R254") (pin "1") (pinfunction "1_1") (pintype "passive"))
      (node (ref "R255") (pin "2") (pinfunction "2_2") (pintype "passive"))
      (node (ref "R259") (pin "2") (pinfunction "2_2") (pintype "passive"))
      (node (ref "R260") (pin "1") (pinfunction "1_1") (pintype "passive"))
      (node (ref "R261") (pin "1") (pinfunction "1_1") (pintype "passive"))
      (node (ref "R262") (pin "1") (pinfunction "1_1") (pintype "passive"))
      (node (ref "R268") (pin "2") (pinfunction "2_2") (pintype "passive"))
      (node (ref "R269") (pin "1") (pinfunction "1_1") (pintype "passive"))
      (node (ref "R270") (pin "1") (pinfunction "1_1") (pintype "passive"))
      (node (ref "TP4") (pin "0") (pinfunction "0_0") (pintype "passive"))
      (node (ref "U23") (pin "8") (pinfunction "8_8") (pintype "passive"))
      (node (ref "U24") (pin "8") (pinfunction "8_8") (pintype "passive"))
      (node (ref "U25") (pin "8") (pinfunction "8_8") (pintype "passive"))
      (node (ref "U26") (pin "8") (pinfunction "8_8") (pintype "passive"))
      (node (ref "U27") (pin "8") (pinfunction "8_8") (pintype "passive"))
      (node (ref "U28") (pin "8") (pinfunction "8_8") (pintype "passive"))
      (node (ref "U29") (pin "8") (pinfunction "8_8") (pintype "passive"))
      (node (ref "U40") (pin "2") (pinfunction "GND_2") (pintype "passive"))
      (node (ref "VR2") (pin "1") (pinfunction "GND_1") (pintype "power_in"))
      (node (ref "VR3") (pin "1") (pinfunction "GND_1") (pintype "power_in"))
    )
    (net (code "16") (name "Net-(C137-Pad2)") (class "Default")
      (node (ref "C137") (pin "2") (pinfunction "2_2") (pintype "passive"))
      (node (ref "U23") (pin "10") (pinfunction "10_10") (pintype "passive"))
    )
    (net (code "17") (name "Net-(C138-Pad2)") (class "Default")
      (node (ref "C138") (pin "2") (pinfunction "2_2") (pintype "passive"))
      (node (ref "U23") (pin "7") (pinfunction "7_7") (pintype "passive"))
    )
    (net (code "18") (name "Net-(C145-Pad2)") (class "Default")
      (node (ref "C145") (pin "2") (pinfunction "2_2") (pintype "passive"))
      (node (ref "U24") (pin "10") (pinfunction "10_10") (pintype "passive"))
    )
    (net (code "19") (name "Net-(C146-Pad2)") (class "Default")
      (node (ref "C146") (pin "2") (pinfunction "2_2") (pintype "passive"))
      (node (ref "U24") (pin "7") (pinfunction "7_7") (pintype "passive"))
    )
    (net (code "20") (name "Net-(C153-Pad2)") (class "Default")
      (node (ref "C153") (pin "2") (pinfunction "2_2") (pintype "passive"))
      (node (ref "U25") (pin "10") (pinfunction "10_10") (pintype "passive"))
    )
    (net (code "21") (name "Net-(C154-Pad2)") (class "Default")
      (node (ref "C154") (pin "2") (pinfunction "2_2") (pintype "passive"))
      (node (ref "U25") (pin "7") (pinfunction "7_7") (pintype "passive"))
    )
    (net (code "22") (name "Net-(C155-Pad2)") (class "Default")
      (node (ref "C155") (pin "2") (pinfunction "2_2") (pintype "passive"))
      (node (ref "U26") (pin "10") (pinfunction "10_10") (pintype "passive"))
    )
    (net (code "23") (name "Net-(C156-Pad2)") (class "Default")
      (node (ref "C156") (pin "2") (pinfunction "2_2") (pintype "passive"))
      (node (ref "U26") (pin "7") (pinfunction "7_7") (pintype "passive"))
    )
    (net (code "24") (name "Net-(C166-Pad2)") (class "Default")
      (node (ref "C166") (pin "2") (pinfunction "2_2") (pintype "passive"))
      (node (ref "U27") (pin "10") (pinfunction "10_10") (pintype "passive"))
    )
    (net (code "25") (name "Net-(C167-Pad2)") (class "Default")
      (node (ref "C167") (pin "2") (pinfunction "2_2") (pintype "passive"))
      (node (ref "U27") (pin "7") (pinfunction "7_7") (pintype "passive"))
    )
    (net (code "26") (name "Net-(C168-Pad2)") (class "Default")
      (node (ref "C168") (pin "2") (pinfunction "2_2") (pintype "passive"))
      (node (ref "U28") (pin "10") (pinfunction "10_10") (pintype "passive"))
    )
    (net (code "27") (name "Net-(C169-Pad2)") (class "Default")
      (node (ref "C169") (pin "2") (pinfunction "2_2") (pintype "passive"))
      (node (ref "U28") (pin "7") (pinfunction "7_7") (pintype "passive"))
    )
    (net (code "28") (name "Net-(C173-Pad2)") (class "Default")
      (node (ref "C173") (pin "2") (pinfunction "2_2") (pintype "passive"))
      (node (ref "U29") (pin "10") (pinfunction "10_10") (pintype "passive"))
    )
    (net (code "29") (name "Net-(C174-Pad2)") (class "Default")
      (node (ref "C174") (pin "2") (pinfunction "2_2") (pintype "passive"))
      (node (ref "U29") (pin "7") (pinfunction "7_7") (pintype "passive"))
    )
    (net (code "30") (name "Net-(U23-EN{slash}UVLO)") (class "Default")
      (node (ref "R217") (pin "1") (pinfunction "1_1") (pintype "passive"))
      (node (ref "R220") (pin "2") (pinfunction "2_2") (pintype "passive"))
      (node (ref "U23") (pin "1") (pinfunction "EN/UVLO_1") (pintype "passive"))
    )
    (net (code "31") (name "Net-(U23-OVLO{slash}OVCSEL)") (class "Default")
      (node (ref "R220") (pin "1") (pinfunction "1_1") (pintype "passive"))
      (node (ref "R221") (pin "2") (pinfunction "2_2") (pintype "passive"))
      (node (ref "U23") (pin "2") (pinfunction "OVLO/OVCSEL_2") (pintype "passive"))
    )
    (net (code "32") (name "Net-(U23-PGTH{slash}~{FLT})") (class "Default")
      (node (ref "R219") (pin "1") (pinfunction "1_1") (pintype "passive"))
      (node (ref "U23") (pin "4") (pinfunction "PGTH/~{FLT}_4") (pintype "passive"))
    )
    (net (code "33") (name "Net-(U23-PG{slash}AUXOFF)") (class "Default")
      (node (ref "R218") (pin "1") (pinfunction "1_1") (pintype "passive"))
      (node (ref "U23") (pin "3") (pinfunction "PG/AUXOFF_3") (pintype "passive"))
    )
    (net (code "34") (name "Net-(U24-EN{slash}UVLO)") (class "Default")
      (node (ref "R225") (pin "1") (pinfunction "1_1") (pintype "passive"))
      (node (ref "R227") (pin "1") (pinfunction "1_1") (pintype "passive"))
      (node (ref "R229") (pin "1") (pinfunction "1_1") (pintype "passive"))
      (node (ref "U24") (pin "1") (pinfunction "EN/UVLO_1") (pintype "passive"))
    )
    (net (code "35") (name "Net-(U24-IN)") (class "Default")
      (node (ref "C141") (pin "2") (pinfunction "2_2") (pintype "passive"))
      (node (ref "JP4") (pin "2") (pinfunction "2_2") (pintype "passive"))
      (node (ref "JP5") (pin "2") (pinfunction "2_2") (pintype "passive"))
      (node (ref "JP6") (pin "1") (pinfunction "1_1") (pintype "passive"))
      (node (ref "R222") (pin "2") (pinfunction "2_2") (pintype "passive"))
      (node (ref "U24") (pin "5") (pinfunction "IN_5") (pintype "passive"))
    )
    (net (code "36") (name "Net-(U24-OVLO{slash}OVCSEL)") (class "Default")
      (node (ref "R222") (pin "1") (pinfunction "1_1") (pintype "passive"))
      (node (ref "R228") (pin "2") (pinfunction "2_2") (pintype "passive"))
      (node (ref "U24") (pin "2") (pinfunction "OVLO/OVCSEL_2") (pintype "passive"))
    )
    (net (code "37") (name "Net-(U24-PGTH{slash}~{FLT})") (class "Default")
      (node (ref "R224") (pin "1") (pinfunction "1_1") (pintype "passive"))
      (node (ref "U24") (pin "4") (pinfunction "PGTH/~{FLT}_4") (pintype "passive"))
    )
    (net (code "38") (name "Net-(U24-PG{slash}AUXOFF)") (class "Default")
      (node (ref "R223") (pin "1") (pinfunction "1_1") (pintype "passive"))
      (node (ref "U24") (pin "3") (pinfunction "PG/AUXOFF_3") (pintype "passive"))
    )
    (net (code "39") (name "Net-(U25-EN{slash}UVLO)") (class "Default")
      (node (ref "R237") (pin "1") (pinfunction "1_1") (pintype "passive"))
      (node (ref "R239") (pin "1") (pinfunction "1_1") (pintype "passive"))
      (node (ref "R243") (pin "1") (pinfunction "1_1") (pintype "passive"))
      (node (ref "U25") (pin "1") (pinfunction "EN/UVLO_1") (pintype "passive"))
    )
    (net (code "40") (name "Net-(U25-OVLO{slash}OVCSEL)") (class "Default")
      (node (ref "R231") (pin "1") (pinfunction "1_1") (pintype "passive"))
      (node (ref "R241") (pin "2") (pinfunction "2_2") (pintype "passive"))
      (node (ref "U25") (pin "2") (pinfunction "OVLO/OVCSEL_2") (pintype "passive"))
    )
    (net (code "41") (name "Net-(U25-PGTH{slash}~{FLT})") (class "Default")
      (node (ref "R234") (pin "1") (pinfunction "1_1") (pintype "passive"))
      (node (ref "U25") (pin "4") (pinfunction "PGTH/~{FLT}_4") (pintype "passive"))
    )
    (net (code "42") (name "Net-(U25-PG{slash}AUXOFF)") (class "Default")
      (node (ref "R233") (pin "1") (pinfunction "1_1") (pintype "passive"))
      (node (ref "U25") (pin "3") (pinfunction "PG/AUXOFF_3") (pintype "passive"))
    )
    (net (code "43") (name "Net-(U26-EN{slash}UVLO)") (class "Default")
      (node (ref "R238") (pin "1") (pinfunction "1_1") (pintype "passive"))
      (node (ref "R240") (pin "1") (pinfunction "1_1") (pintype "passive"))
      (node (ref "R244") (pin "1") (pinfunction "1_1") (pintype "passive"))
      (node (ref "U26") (pin "1") (pinfunction "EN/UVLO_1") (pintype "passive"))
    )
    (net (code "44") (name "Net-(U26-OVLO{slash}OVCSEL)") (class "Default")
      (node (ref "R232") (pin "1") (pinfunction "1_1") (pintype "passive"))
      (node (ref "R242") (pin "2") (pinfunction "2_2") (pintype "passive"))
      (node (ref "U26") (pin "2") (pinfunction "OVLO/OVCSEL_2") (pintype "passive"))
    )
    (net (code "45") (name "Net-(U26-PGTH{slash}~{FLT})") (class "Default")
      (node (ref "R236") (pin "1") (pinfunction "1_1") (pintype "passive"))
      (node (ref "U26") (pin "4") (pinfunction "PGTH/~{FLT}_4") (pintype "passive"))
    )
    (net (code "46") (name "Net-(U26-PG{slash}AUXOFF)") (class "Default")
      (node (ref "R235") (pin "1") (pinfunction "1_1") (pintype "passive"))
      (node (ref "U26") (pin "3") (pinfunction "PG/AUXOFF_3") (pintype "passive"))
    )
    (net (code "47") (name "Net-(U27-EN{slash}UVLO)") (class "Default")
      (node (ref "R250") (pin "1") (pinfunction "1_1") (pintype "passive"))
      (node (ref "R251") (pin "1") (pinfunction "1_1") (pintype "passive"))
      (node (ref "R255") (pin "1") (pinfunction "1_1") (pintype "passive"))
      (node (ref "U27") (pin "1") (pinfunction "EN/UVLO_1") (pintype "passive"))
    )
    (net (code "48") (name "Net-(U27-OVLO{slash}OVCSEL)") (class "Default")
      (node (ref "R247") (pin "1") (pinfunction "1_1") (pintype "passive"))
      (node (ref "R254") (pin "2") (pinfunction "2_2") (pintype "passive"))
      (node (ref "U27") (pin "2") (pinfunction "OVLO/OVCSEL_2") (pintype "passive"))
    )
    (net (code "49") (name "Net-(U27-PGTH{slash}~{FLT})") (class "Default")
      (node (ref "R249") (pin "1") (pinfunction "1_1") (pintype "passive"))
      (node (ref "U27") (pin "4") (pinfunction "PGTH/~{FLT}_4") (pintype "passive"))
    )
    (net (code "50") (name "Net-(U27-PG{slash}AUXOFF)") (class "Default")
      (node (ref "R248") (pin "1") (pinfunction "1_1") (pintype "passive"))
      (node (ref "U27") (pin "3") (pinfunction "PG/AUXOFF_3") (pintype "passive"))
    )
    (net (code "51") (name "Net-(U28-EN{slash}UVLO)") (class "Default")
      (node (ref "R252") (pin "1") (pinfunction "1_1") (pintype "passive"))
      (node (ref "R258") (pin "1") (pinfunction "1_1") (pintype "passive"))
      (node (ref "R259") (pin "1") (pinfunction "1_1") (pintype "passive"))
      (node (ref "U28") (pin "1") (pinfunction "EN/UVLO_1") (pintype "passive"))
    )
    (net (code "52") (name "Net-(U28-OVLO{slash}OVCSEL)") (class "Default")
      (node (ref "R253") (pin "1") (pinfunction "1_1") (pintype "passive"))
      (node (ref "R260") (pin "2") (pinfunction "2_2") (pintype "passive"))
      (node (ref "U28") (pin "2") (pinfunction "OVLO/OVCSEL_2") (pintype "passive"))
    )
    (net (code "53") (name "Net-(U28-PGTH{slash}~{FLT})") (class "Default")
      (node (ref "R257") (pin "1") (pinfunction "1_1") (pintype "passive"))
      (node (ref "U28") (pin "4") (pinfunction "PGTH/~{FLT}_4") (pintype "passive"))
    )
    (net (code "54") (name "Net-(U28-PG{slash}AUXOFF)") (class "Default")
      (node (ref "R256") (pin "1") (pinfunction "1_1") (pintype "passive"))
      (node (ref "U28") (pin "3") (pinfunction "PG/AUXOFF_3") (pintype "passive"))
    )
    (net (code "55") (name "Net-(U29-EN{slash}UVLO)") (class "Default")
      (node (ref "R263") (pin "1") (pinfunction "1_1") (pintype "passive"))
      (node (ref "R267") (pin "1") (pinfunction "1_1") (pintype "passive"))
      (node (ref "R268") (pin "1") (pinfunction "1_1") (pintype "passive"))
      (node (ref "U29") (pin "1") (pinfunction "EN/UVLO_1") (pintype "passive"))
    )
    (net (code "56") (name "Net-(U29-OVLO{slash}OVCSEL)") (class "Default")
      (node (ref "R264") (pin "1") (pinfunction "1_1") (pintype "passive"))
      (node (ref "R269") (pin "2") (pinfunction "2_2") (pintype "passive"))
      (node (ref "U29") (pin "2") (pinfunction "OVLO/OVCSEL_2") (pintype "passive"))
    )
    (net (code "57") (name "Net-(U29-PGTH{slash}~{FLT})") (class "Default")
      (node (ref "R266") (pin "1") (pinfunction "1_1") (pintype "passive"))
      (node (ref "U29") (pin "4") (pinfunction "PGTH/~{FLT}_4") (pintype "passive"))
    )
    (net (code "58") (name "Net-(U29-PG{slash}AUXOFF)") (class "Default")
      (node (ref "R265") (pin "1") (pinfunction "1_1") (pintype "passive"))
      (node (ref "U29") (pin "3") (pinfunction "PG/AUXOFF_3") (pintype "passive"))
    )
    (net (code "59") (name "Net-(U40-EN)") (class "Default")
      (node (ref "R295") (pin "1") (pinfunction "1_1") (pintype "passive"))
      (node (ref "U40") (pin "3") (pinfunction "EN_3") (pintype "passive"))
    )
    (net (code "60") (name "POW_ONOFF_5V") (class "Default")
      (node (ref "R237") (pin "2") (pinfunction "2_2") (pintype "passive"))
    )
    (net (code "61") (name "POW_ONOFF_HD4") (class "Default")
      (node (ref "R267") (pin "2") (pinfunction "2_2") (pintype "passive"))
    )
    (net (code "62") (name "POW_ONOFF_Laser") (class "Default")
      (node (ref "R250") (pin "2") (pinfunction "2_2") (pintype "passive"))
    )
    (net (code "63") (name "POW_ONOFF_Photo") (class "Default")
      (node (ref "R238") (pin "2") (pinfunction "2_2") (pintype "passive"))
    )
    (net (code "64") (name "POW_ONOFF_Solenoid") (class "Default")
      (node (ref "R225") (pin "2") (pinfunction "2_2") (pintype "passive"))
    )
    (net (code "65") (name "POW_ONOFF_TEC") (class "Default")
      (node (ref "R258") (pin "2") (pinfunction "2_2") (pintype "passive"))
    )
    (net (code "66") (name "eFUSE_ILIM_3{slash}5V_Solenoid") (class "Default")
      (node (ref "R230") (pin "2") (pinfunction "2_2") (pintype "passive"))
      (node (ref "U24") (pin "9") (pinfunction "9_9") (pintype "passive"))
    )
    (net (code "67") (name "eFUSE_ILIM_5V") (class "Default")
      (node (ref "R245") (pin "2") (pinfunction "2_2") (pintype "passive"))
      (node (ref "U25") (pin "9") (pinfunction "9_9") (pintype "passive"))
    )
    (net (code "68") (name "eFUSE_ILIM_5V_HD4") (class "Default")
      (node (ref "R270") (pin "2") (pinfunction "2_2") (pintype "passive"))
      (node (ref "U29") (pin "9") (pinfunction "9_9") (pintype "passive"))
    )
    (net (code "69") (name "eFUSE_ILIM_5V_MCU") (class "Default")
      (node (ref "R226") (pin "2") (pinfunction "2_2") (pintype "passive"))
      (node (ref "U23") (pin "9") (pinfunction "9_9") (pintype "passive"))
    )
    (net (code "70") (name "eFUSE_ILIM_5V_TEC") (class "Default")
      (node (ref "R262") (pin "2") (pinfunction "2_2") (pintype "passive"))
      (node (ref "U28") (pin "9") (pinfunction "9_9") (pintype "passive"))
    )
    (net (code "71") (name "eFUSE_ILIM_12V_Laser") (class "Default")
      (node (ref "R261") (pin "2") (pinfunction "2_2") (pintype "passive"))
      (node (ref "U27") (pin "9") (pinfunction "9_9") (pintype "passive"))
    )
    (net (code "72") (name "eFUSE_ILIM_12V_Photo") (class "Default")
      (node (ref "R246") (pin "2") (pinfunction "2_2") (pintype "passive"))
      (node (ref "U26") (pin "9") (pinfunction "9_9") (pintype "passive"))
    )
    (net (code "73") (name "unconnected-(U40-NC-Pad4)") (class "Default")
      (node (ref "U40") (pin "4") (pinfunction "NC_4") (pintype "passive+no_connect"))
    )
  )
)
